# HolderDog_Simetric.net
KiCad netlist of a schematic drawn in Altium Designer
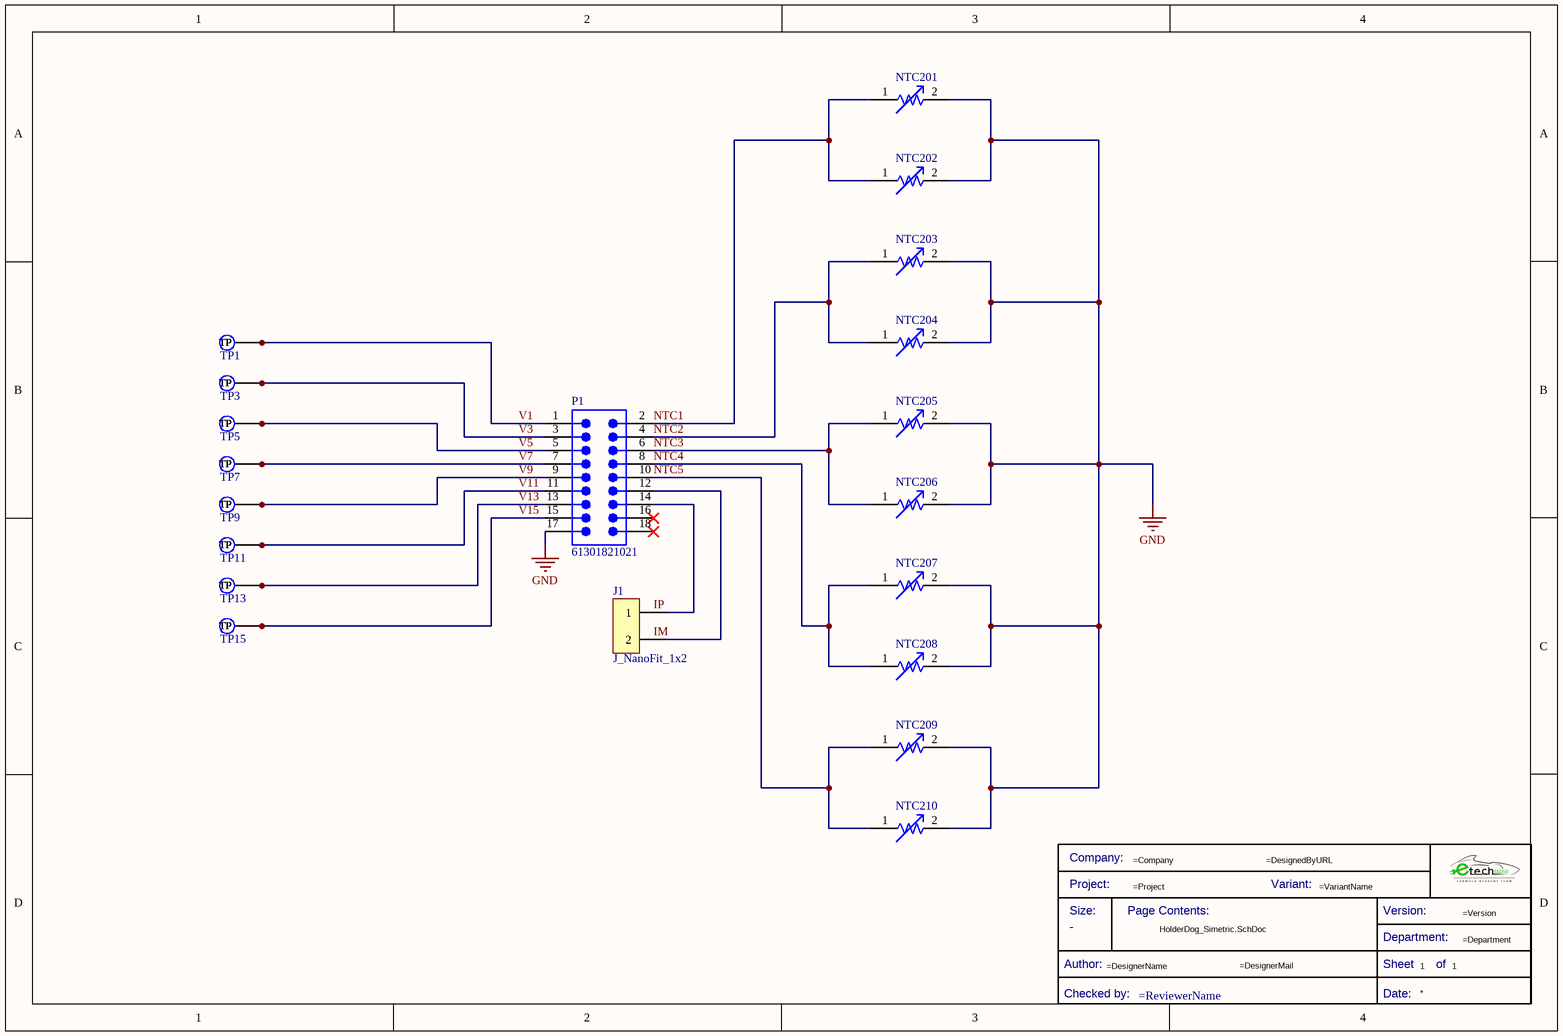
[diagram p0: HolderDog_Simetric.SchDoc]

(export (version "E")
  (design (tool "Eeschema 10.0.6"))
  (components
    (comp (ref "*")
      (value "Title Block_template")
      (description "Standard Title Block")
      (fields
        (field (name "SIZE") "-")
        (field (name ".CREATOR") "GP")
        (field (name ".PCBCHECK") "GP")
        (field (name ".SCHCHECK") "GP")
      )
      (libsource (lib "e-Tech_Racing") (part "Title Block_template"))
    )
    (comp (ref "J1")
      (value "J_NanoFit_1x2")
      (footprint "FP-105309-1102-MFG")
      (description "Conn HDR 2 POS 2.5mm Solder ST Thru-Hole 2 Terminal 1 Port Nano-Fit Tray")
      (libsource (lib "EMEA- E-Tech Racing- I'Escola d'Enginyeria de Barcelona Est") (part "Molex Nano-Fit"))
    )
    (comp (ref "NTC201")
      (value "NTC SMD 0805")
      (footprint "RESC2012X10N")
      (description "NTC 0805 package 10kR")
      (libsource (lib "EMEA- E-Tech Racing- I'Escola d'Enginyeria de Barcelona Est") (part "0805"))
    )
    (comp (ref "NTC202")
      (value "NTC SMD 0805")
      (footprint "RESC2012X10N")
      (description "NTC 0805 package 10kR")
      (libsource (lib "EMEA- E-Tech Racing- I'Escola d'Enginyeria de Barcelona Est") (part "0805"))
    )
    (comp (ref "NTC203")
      (value "NTC SMD 0805")
      (footprint "RESC2012X10N")
      (description "NTC 0805 package 10kR")
      (libsource (lib "EMEA- E-Tech Racing- I'Escola d'Enginyeria de Barcelona Est") (part "0805"))
    )
    (comp (ref "NTC204")
      (value "NTC SMD 0805")
      (footprint "RESC2012X10N")
      (description "NTC 0805 package 10kR")
      (libsource (lib "EMEA- E-Tech Racing- I'Escola d'Enginyeria de Barcelona Est") (part "0805"))
    )
    (comp (ref "NTC205")
      (value "NTC SMD 0805")
      (footprint "RESC2012X10N")
      (description "NTC 0805 package 10kR")
      (libsource (lib "EMEA- E-Tech Racing- I'Escola d'Enginyeria de Barcelona Est") (part "0805"))
    )
    (comp (ref "NTC206")
      (value "NTC SMD 0805")
      (footprint "RESC2012X10N")
      (description "NTC 0805 package 10kR")
      (libsource (lib "EMEA- E-Tech Racing- I'Escola d'Enginyeria de Barcelona Est") (part "0805"))
    )
    (comp (ref "NTC207")
      (value "NTC SMD 0805")
      (footprint "RESC2012X10N")
      (description "NTC 0805 package 10kR")
      (libsource (lib "EMEA- E-Tech Racing- I'Escola d'Enginyeria de Barcelona Est") (part "0805"))
    )
    (comp (ref "NTC208")
      (value "NTC SMD 0805")
      (footprint "RESC2012X10N")
      (description "NTC 0805 package 10kR")
      (libsource (lib "EMEA- E-Tech Racing- I'Escola d'Enginyeria de Barcelona Est") (part "0805"))
    )
    (comp (ref "NTC209")
      (value "NTC SMD 0805")
      (footprint "RESC2012X10N")
      (description "NTC 0805 package 10kR")
      (libsource (lib "EMEA- E-Tech Racing- I'Escola d'Enginyeria de Barcelona Est") (part "0805"))
    )
    (comp (ref "NTC210")
      (value "NTC SMD 0805")
      (footprint "RESC2012X10N")
      (description "NTC 0805 package 10kR")
      (libsource (lib "EMEA- E-Tech Racing- I'Escola d'Enginyeria de Barcelona Est") (part "0805"))
    )
    (comp (ref "P1")
      (value "61301821021")
      (footprint "61301821021")
      (libsource (lib "EMEA- E-Tech Racing- I'Escola d'Enginyeria de Barcelona Est") (part "Header_Male_2R_18P"))
    )
    (comp (ref "TP1")
      (value "Test Point")
      (footprint "TESTPOINT_WIDE")
      (description "TestPoint 5x5mm")
      (libsource (lib "e-Tech_Racing") (part "TestPoint_Wide"))
    )
    (comp (ref "TP3")
      (value "Test Point")
      (footprint "TESTPOINT_WIDE")
      (description "TestPoint 5x5mm")
      (libsource (lib "e-Tech_Racing") (part "TestPoint_Wide"))
    )
    (comp (ref "TP5")
      (value "Test Point")
      (footprint "TESTPOINT_WIDE")
      (description "TestPoint 5x5mm")
      (libsource (lib "e-Tech_Racing") (part "TestPoint_Wide"))
    )
    (comp (ref "TP7")
      (value "Test Point")
      (footprint "TESTPOINT_WIDE")
      (description "TestPoint 5x5mm")
      (libsource (lib "e-Tech_Racing") (part "TestPoint_Wide"))
    )
    (comp (ref "TP9")
      (value "Test Point")
      (footprint "TESTPOINT_WIDE")
      (description "TestPoint 5x5mm")
      (libsource (lib "e-Tech_Racing") (part "TestPoint_Wide"))
    )
    (comp (ref "TP11")
      (value "Test Point")
      (footprint "TESTPOINT_WIDE")
      (description "TestPoint 5x5mm")
      (libsource (lib "e-Tech_Racing") (part "TestPoint_Wide"))
    )
    (comp (ref "TP13")
      (value "Test Point")
      (footprint "TESTPOINT_WIDE")
      (description "TestPoint 5x5mm")
      (libsource (lib "e-Tech_Racing") (part "TestPoint_Wide"))
    )
    (comp (ref "TP15")
      (value "Test Point")
      (footprint "TESTPOINT_WIDE")
      (description "TestPoint 5x5mm")
      (libsource (lib "e-Tech_Racing") (part "TestPoint_Wide"))
    )
  )
  (nets
    (net (code "3") (name "/NTC1") (class "Default")
      (node (ref "NTC201") (pin "1") (pinfunction "1_1") (pintype "passive"))
      (node (ref "NTC202") (pin "1") (pinfunction "1_1") (pintype "passive"))
      (node (ref "P1") (pin "2") (pinfunction "2_2") (pintype "passive"))
    )
    (net (code "4") (name "/NTC2") (class "Default")
      (node (ref "NTC203") (pin "1") (pinfunction "1_1") (pintype "passive"))
      (node (ref "NTC204") (pin "1") (pinfunction "1_1") (pintype "passive"))
      (node (ref "P1") (pin "4") (pinfunction "4_4") (pintype "passive"))
    )
    (net (code "5") (name "/NTC3") (class "Default")
      (node (ref "NTC205") (pin "1") (pinfunction "1_1") (pintype "passive"))
      (node (ref "NTC206") (pin "1") (pinfunction "1_1") (pintype "passive"))
      (node (ref "P1") (pin "6") (pinfunction "6_6") (pintype "passive"))
    )
    (net (code "6") (name "/NTC4") (class "Default")
      (node (ref "NTC207") (pin "1") (pinfunction "1_1") (pintype "passive"))
      (node (ref "NTC208") (pin "1") (pinfunction "1_1") (pintype "passive"))
      (node (ref "P1") (pin "8") (pinfunction "8_8") (pintype "passive"))
    )
    (net (code "7") (name "/NTC5") (class "Default")
      (node (ref "NTC209") (pin "1") (pinfunction "1_1") (pintype "passive"))
      (node (ref "NTC210") (pin "1") (pinfunction "1_1") (pintype "passive"))
      (node (ref "P1") (pin "10") (pinfunction "10_10") (pintype "passive"))
    )
    (net (code "8") (name "/V1") (class "Default")
      (node (ref "P1") (pin "1") (pinfunction "1_1") (pintype "passive"))
      (node (ref "TP1") (pin "1") (pinfunction "TP_1") (pintype "passive"))
    )
    (net (code "9") (name "/V3") (class "Default")
      (node (ref "P1") (pin "3") (pinfunction "3_3") (pintype "passive"))
      (node (ref "TP3") (pin "1") (pinfunction "TP_1") (pintype "passive"))
    )
    (net (code "10") (name "/V5") (class "Default")
      (node (ref "P1") (pin "5") (pinfunction "5_5") (pintype "passive"))
      (node (ref "TP5") (pin "1") (pinfunction "TP_1") (pintype "passive"))
    )
    (net (code "11") (name "/V7") (class "Default")
      (node (ref "P1") (pin "7") (pinfunction "7_7") (pintype "passive"))
      (node (ref "TP7") (pin "1") (pinfunction "TP_1") (pintype "passive"))
    )
    (net (code "12") (name "/V9") (class "Default")
      (node (ref "P1") (pin "9") (pinfunction "9_9") (pintype "passive"))
      (node (ref "TP9") (pin "1") (pinfunction "TP_1") (pintype "passive"))
    )
    (net (code "13") (name "/V11") (class "Default")
      (node (ref "P1") (pin "11") (pinfunction "11_11") (pintype "passive"))
      (node (ref "TP11") (pin "1") (pinfunction "TP_1") (pintype "passive"))
    )
    (net (code "14") (name "/V13") (class "Default")
      (node (ref "P1") (pin "13") (pinfunction "13_13") (pintype "passive"))
      (node (ref "TP13") (pin "1") (pinfunction "TP_1") (pintype "passive"))
    )
    (net (code "15") (name "/V15") (class "Default")
      (node (ref "P1") (pin "15") (pinfunction "15_15") (pintype "passive"))
      (node (ref "TP15") (pin "1") (pinfunction "TP_1") (pintype "passive"))
    )
    (net (code "16") (name "GND") (class "Default")
      (node (ref "NTC201") (pin "2") (pinfunction "2_2") (pintype "passive"))
      (node (ref "NTC202") (pin "2") (pinfunction "2_2") (pintype "passive"))
      (node (ref "NTC203") (pin "2") (pinfunction "2_2") (pintype "passive"))
      (node (ref "NTC204") (pin "2") (pinfunction "2_2") (pintype "passive"))
      (node (ref "NTC205") (pin "2") (pinfunction "2_2") (pintype "passive"))
      (node (ref "NTC206") (pin "2") (pinfunction "2_2") (pintype "passive"))
      (node (ref "NTC207") (pin "2") (pinfunction "2_2") (pintype "passive"))
      (node (ref "NTC208") (pin "2") (pinfunction "2_2") (pintype "passive"))
      (node (ref "NTC209") (pin "2") (pinfunction "2_2") (pintype "passive"))
      (node (ref "NTC210") (pin "2") (pinfunction "2_2") (pintype "passive"))
      (node (ref "P1") (pin "17") (pinfunction "17_17") (pintype "passive"))
    )
    (net (code "17") (name "Net-(J1-Pad1)") (class "Default")
      (node (ref "J1") (pin "1") (pinfunction "1_1") (pintype "passive"))
      (node (ref "P1") (pin "14") (pinfunction "14_14") (pintype "passive"))
    )
    (net (code "18") (name "Net-(J1-Pad2)") (class "Default")
      (node (ref "J1") (pin "2") (pinfunction "2_2") (pintype "passive"))
      (node (ref "P1") (pin "12") (pinfunction "12_12") (pintype "passive"))
    )
    (net (code "19") (name "unconnected-(P1-Pad16)") (class "Default")
      (node (ref "P1") (pin "16") (pinfunction "16_16") (pintype "passive+no_connect"))
    )
    (net (code "20") (name "unconnected-(P1-Pad18)") (class "Default")
      (node (ref "P1") (pin "18") (pinfunction "18_18") (pintype "passive+no_connect"))
    )
  )
)
